# ZeroGecko110BreakoutV1_1.net
KiCad netlist of a schematic drawn in EAGLE
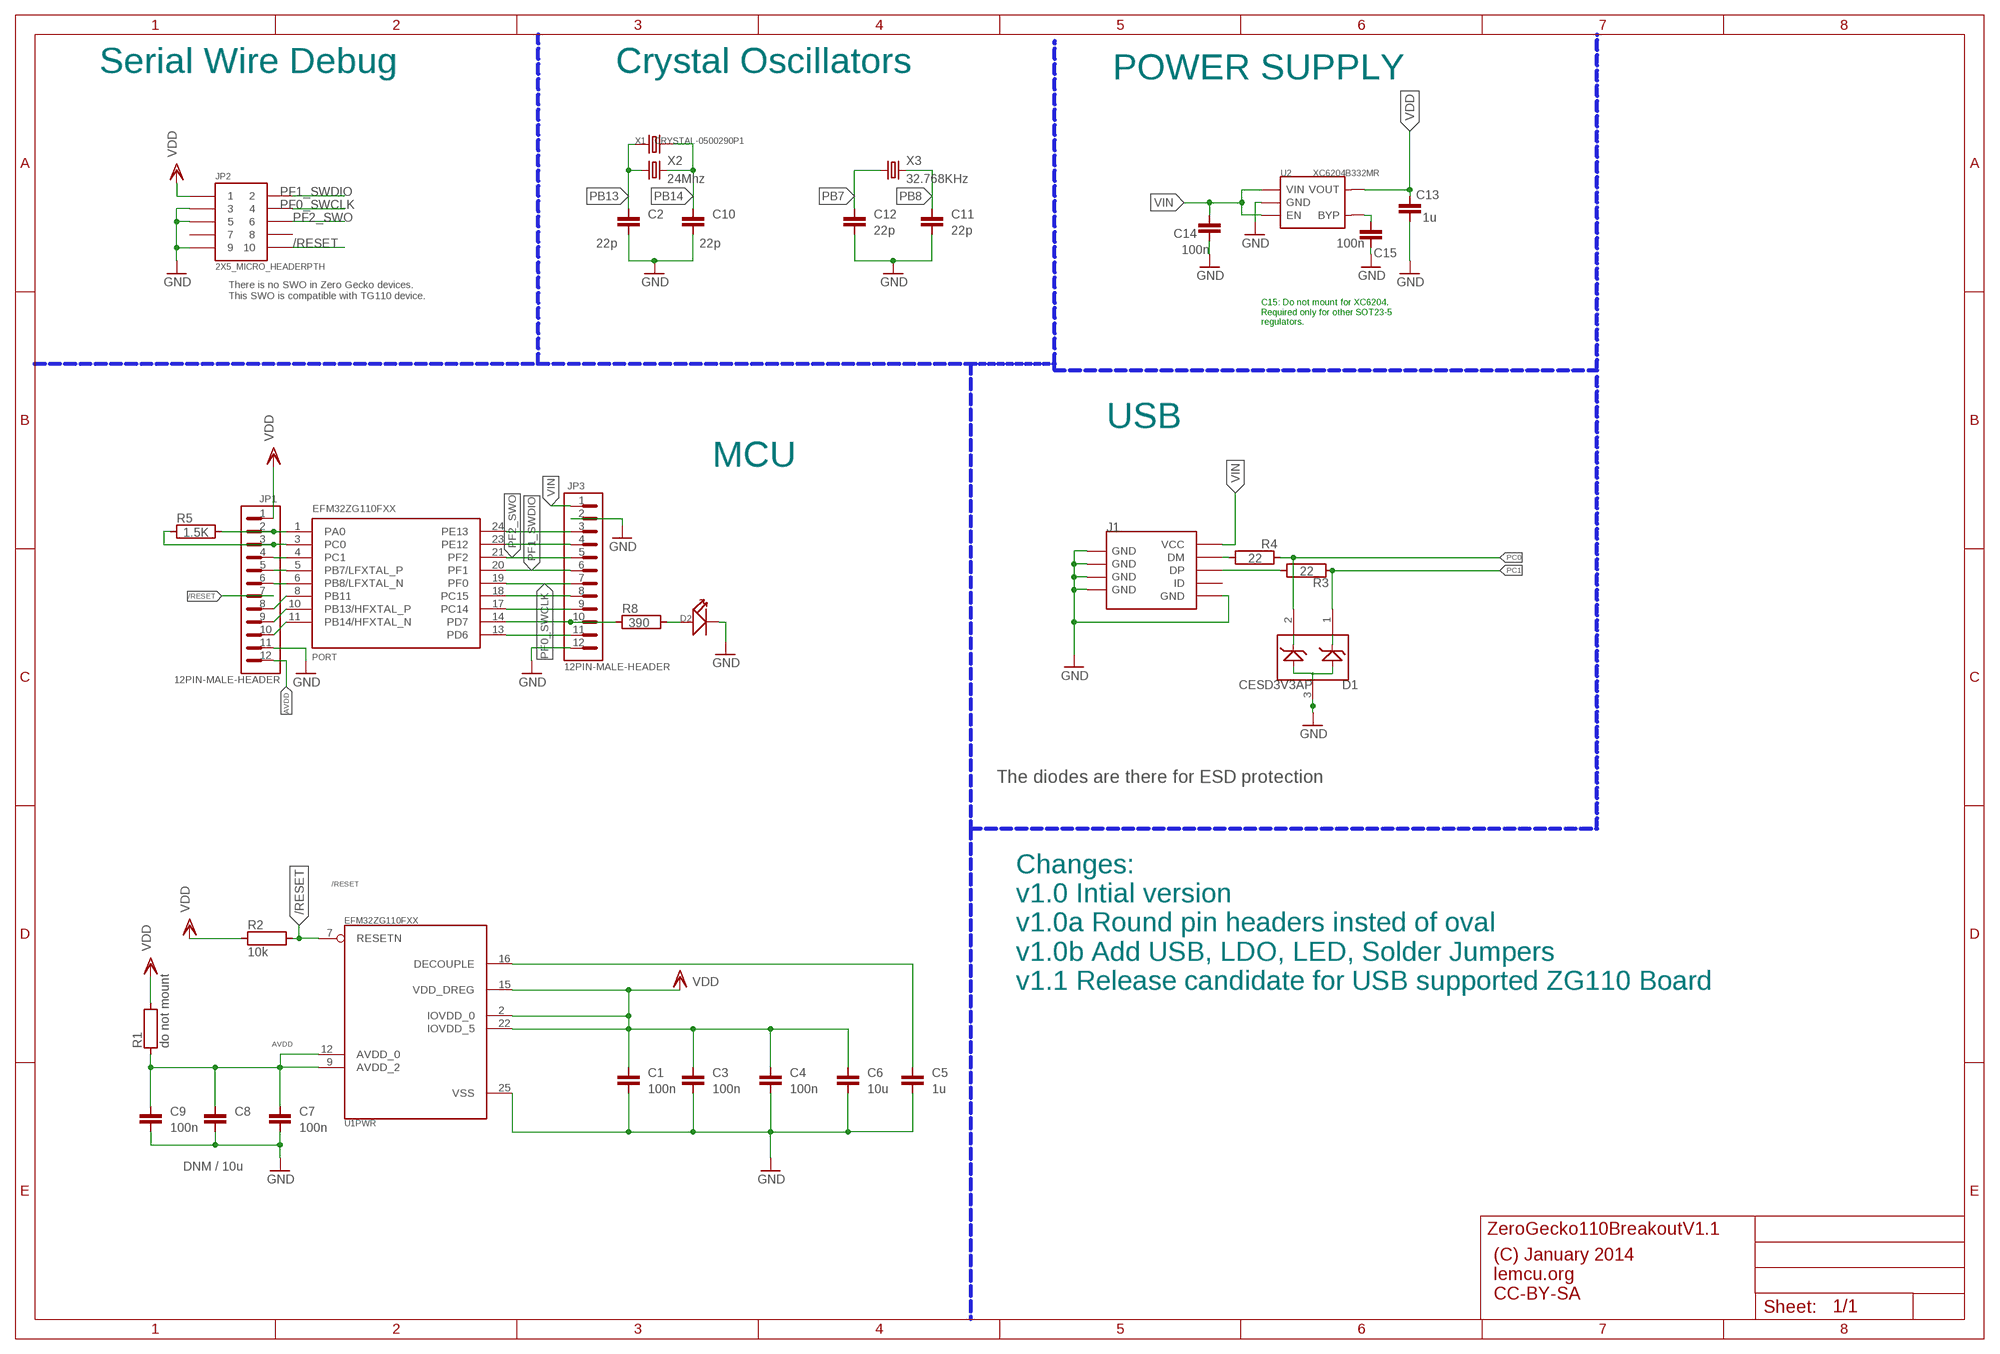
[diagram p0: schematic, sheet 1]

(export (version "E")
  (design (tool "Eeschema 10.0.6"))
  (components
    (comp (ref "C1")
      (value "100n")
      (footprint "eagle-import:C0603")
      (libsource (lib "eagle-import") (part "C0603"))
    )
    (comp (ref "C2")
      (value "22p")
      (footprint "eagle-import:C0603")
      (libsource (lib "eagle-import") (part "C0603"))
    )
    (comp (ref "C3")
      (value "100n")
      (footprint "eagle-import:C0603")
      (libsource (lib "eagle-import") (part "C0603"))
    )
    (comp (ref "C4")
      (value "100n")
      (footprint "eagle-import:C0603")
      (libsource (lib "eagle-import") (part "C0603"))
    )
    (comp (ref "C5")
      (value "1u")
      (footprint "eagle-import:C0805")
      (libsource (lib "eagle-import") (part "C0805"))
    )
    (comp (ref "C6")
      (value "10u")
      (footprint "eagle-import:C0805")
      (libsource (lib "eagle-import") (part "C0805"))
    )
    (comp (ref "C7")
      (value "100n")
      (footprint "eagle-import:C0603")
      (libsource (lib "eagle-import") (part "C0603"))
    )
    (comp (ref "C8")
      (value "DNM / 10u")
      (footprint "eagle-import:C0805")
      (libsource (lib "eagle-import") (part "C0805"))
    )
    (comp (ref "C9")
      (value "100n")
      (footprint "eagle-import:C0603")
      (libsource (lib "eagle-import") (part "C0603"))
    )
    (comp (ref "C10")
      (value "22p")
      (footprint "eagle-import:C0603")
      (libsource (lib "eagle-import") (part "C0603"))
    )
    (comp (ref "C11")
      (value "22p")
      (footprint "eagle-import:C0603")
      (libsource (lib "eagle-import") (part "C0603"))
    )
    (comp (ref "C12")
      (value "22p")
      (footprint "eagle-import:C0603")
      (libsource (lib "eagle-import") (part "C0603"))
    )
    (comp (ref "C13")
      (value "1u")
      (footprint "eagle-import:C0805")
      (libsource (lib "eagle-import") (part "C0805"))
    )
    (comp (ref "C14")
      (value "100n")
      (footprint "eagle-import:C0805")
      (libsource (lib "eagle-import") (part "C0805"))
    )
    (comp (ref "C15")
      (value "100n")
      (footprint "eagle-import:C0805")
      (libsource (lib "eagle-import") (part "C0805"))
    )
    (comp (ref "D1")
      (value "CESD3V3AP")
      (footprint "eagle-import:SOT23")
      (libsource (lib "eagle-import") (part "D-ESD-3P"))
    )
    (comp (ref "D2")
      (value "LED")
      (footprint "eagle-import:LED0603")
      (libsource (lib "eagle-import") (part "LED"))
    )
    (comp (ref "J1")
      (value "USB-MINIUSB-5P-MICRO")
      (footprint "eagle-import:MICRO-USB")
      (libsource (lib "eagle-import") (part "USB-MINIUSB-5P-MICRO"))
    )
    (comp (ref "JP1")
      (value "12PIN-MALE-HEADER")
      (footprint "eagle-import:12P-2.54MM")
      (libsource (lib "eagle-import") (part "12PIN-MALE-HEADER"))
    )
    (comp (ref "JP2")
      (value "2X5_MICRO_HEADERPTH")
      (footprint "eagle-import:2X5_1.27MM_PTH")
      (libsource (lib "eagle-import") (part "2X5_MICRO_HEADERPTH"))
    )
    (comp (ref "JP3")
      (value "12PIN-MALE-HEADER")
      (footprint "eagle-import:12P-2.54MM")
      (libsource (lib "eagle-import") (part "12PIN-MALE-HEADER"))
    )
    (comp (ref "R1")
      (value "do not mount")
      (footprint "eagle-import:R0805")
      (libsource (lib "eagle-import") (part "R0805"))
    )
    (comp (ref "R2")
      (value "10k")
      (footprint "eagle-import:R0603")
      (libsource (lib "eagle-import") (part "R0603"))
    )
    (comp (ref "R3")
      (value "22")
      (footprint "eagle-import:R0603")
      (libsource (lib "eagle-import") (part "R0603"))
    )
    (comp (ref "R4")
      (value "22")
      (footprint "eagle-import:R0603")
      (libsource (lib "eagle-import") (part "R0603"))
    )
    (comp (ref "R5")
      (value "1.5K")
      (footprint "eagle-import:R0603")
      (libsource (lib "eagle-import") (part "R0603"))
    )
    (comp (ref "R8")
      (value "390")
      (footprint "eagle-import:R0603")
      (libsource (lib "eagle-import") (part "R0603"))
    )
    (comp (ref "U1")
      (value "EFM32ZG110FXX")
      (footprint "eagle-import:QFN24")
      (libsource (lib "eagle-import") (part "EFM32ZG110FXX"))
    )
    (comp (ref "U2")
      (value "XC6204B332MR")
      (footprint "eagle-import:SOT23-5")
      (libsource (lib "eagle-import") (part "XC6204B332MR"))
    )
    (comp (ref "X1")
      (value "CRYSTAL-0500290P1")
      (footprint "eagle-import:2P-SMD-5.0X3.2")
      (libsource (lib "eagle-import") (part "CRYSTAL-0500290P1"))
    )
    (comp (ref "X2")
      (value "24Mhz")
      (footprint "eagle-import:HC49U-V")
      (libsource (lib "eagle-import") (part "CRYSTALHC49U-V"))
    )
    (comp (ref "X3")
      (value "32.768KHz")
      (footprint "eagle-import:TC26V")
      (libsource (lib "eagle-import") (part "CRYSTALTC26V"))
    )
  )
  (nets
    (net (code "1") (name "AVDD") (class "Default")
      (node (ref "C7") (pin "2") (pinfunction "2_2") (pintype "passive"))
      (node (ref "C8") (pin "2") (pinfunction "2_2") (pintype "passive"))
      (node (ref "C9") (pin "2") (pinfunction "2_2") (pintype "passive"))
      (node (ref "JP1") (pin "12") (pinfunction "12_12") (pintype "bidirectional"))
      (node (ref "R1") (pin "1") (pinfunction "1_1") (pintype "passive"))
      (node (ref "U1") (pin "12") (pinfunction "AVDD_0_12") (pintype "power_in"))
      (node (ref "U1") (pin "9") (pinfunction "AVDD_2_9") (pintype "power_in"))
    )
    (net (code "2") (name "GND") (class "Default")
      (node (ref "C1") (pin "1") (pinfunction "1_1") (pintype "passive"))
      (node (ref "C10") (pin "1") (pinfunction "1_1") (pintype "passive"))
      (node (ref "C11") (pin "1") (pinfunction "1_1") (pintype "passive"))
      (node (ref "C12") (pin "1") (pinfunction "1_1") (pintype "passive"))
      (node (ref "C13") (pin "1") (pinfunction "1_1") (pintype "passive"))
      (node (ref "C14") (pin "1") (pinfunction "1_1") (pintype "passive"))
      (node (ref "C15") (pin "1") (pinfunction "1_1") (pintype "passive"))
      (node (ref "C2") (pin "1") (pinfunction "1_1") (pintype "passive"))
      (node (ref "C3") (pin "1") (pinfunction "1_1") (pintype "passive"))
      (node (ref "C4") (pin "1") (pinfunction "1_1") (pintype "passive"))
      (node (ref "C5") (pin "1") (pinfunction "1_1") (pintype "passive"))
      (node (ref "C6") (pin "1") (pinfunction "1_1") (pintype "passive"))
      (node (ref "C7") (pin "1") (pinfunction "1_1") (pintype "passive"))
      (node (ref "C8") (pin "1") (pinfunction "1_1") (pintype "passive"))
      (node (ref "C9") (pin "1") (pinfunction "1_1") (pintype "passive"))
      (node (ref "D1") (pin "3") (pinfunction "3_3") (pintype "bidirectional"))
      (node (ref "D2") (pin "-") (pinfunction "-_-") (pintype "passive"))
      (node (ref "J1") (pin "5") (pinfunction "GND_5") (pintype "bidirectional"))
      (node (ref "J1") (pin "S1") (pinfunction "GND_S1") (pintype "bidirectional"))
      (node (ref "J1") (pin "S2") (pinfunction "GND_S2") (pintype "bidirectional"))
      (node (ref "J1") (pin "S3") (pinfunction "GND_S3") (pintype "bidirectional"))
      (node (ref "J1") (pin "S4") (pinfunction "GND_S4") (pintype "bidirectional"))
      (node (ref "J1") (pin "S5") (pinfunction "GND_S5") (pintype "bidirectional"))
      (node (ref "J1") (pin "S6") (pinfunction "GND_S6") (pintype "bidirectional"))
      (node (ref "JP1") (pin "11") (pinfunction "11_11") (pintype "bidirectional"))
      (node (ref "JP2") (pin "3") (pinfunction "3_3") (pintype "bidirectional"))
      (node (ref "JP2") (pin "5") (pinfunction "5_5") (pintype "bidirectional"))
      (node (ref "JP2") (pin "9") (pinfunction "9_9") (pintype "bidirectional"))
      (node (ref "JP3") (pin "12") (pinfunction "12_12") (pintype "bidirectional"))
      (node (ref "JP3") (pin "2") (pinfunction "2_2") (pintype "bidirectional"))
      (node (ref "U1") (pin "25") (pinfunction "VSS_25") (pintype "power_in"))
      (node (ref "U2") (pin "2") (pinfunction "GND_2") (pintype "bidirectional"))
    )
    (net (code "3") (name "Net-(D2-Pad+)") (class "Default")
      (node (ref "D2") (pin "+") (pinfunction "+_+") (pintype "passive"))
      (node (ref "R8") (pin "2") (pinfunction "2_2") (pintype "passive"))
    )
    (net (code "4") (name "Net-(J1-DM)") (class "Default")
      (node (ref "J1") (pin "2") (pinfunction "DM_2") (pintype "bidirectional"))
      (node (ref "R4") (pin "1") (pinfunction "1_1") (pintype "passive"))
    )
    (net (code "5") (name "Net-(J1-DP)") (class "Default")
      (node (ref "J1") (pin "3") (pinfunction "DP_3") (pintype "bidirectional"))
      (node (ref "R3") (pin "1") (pinfunction "1_1") (pintype "passive"))
    )
    (net (code "6") (name "Net-(U1A-PA0)") (class "Default")
      (node (ref "JP1") (pin "2") (pinfunction "2_2") (pintype "bidirectional"))
      (node (ref "R5") (pin "2") (pinfunction "2_2") (pintype "passive"))
      (node (ref "U1") (pin "1") (pinfunction "PA0_1") (pintype "bidirectional"))
    )
    (net (code "7") (name "Net-(U1A-PB11)") (class "Default")
      (node (ref "JP1") (pin "8") (pinfunction "8_8") (pintype "bidirectional"))
      (node (ref "U1") (pin "8") (pinfunction "PB11_8") (pintype "bidirectional"))
    )
    (net (code "8") (name "Net-(U1A-PC14)") (class "Default")
      (node (ref "JP3") (pin "9") (pinfunction "9_9") (pintype "bidirectional"))
      (node (ref "U1") (pin "17") (pinfunction "PC14_17") (pintype "bidirectional"))
    )
    (net (code "9") (name "Net-(U1A-PC15)") (class "Default")
      (node (ref "JP3") (pin "8") (pinfunction "8_8") (pintype "bidirectional"))
      (node (ref "U1") (pin "18") (pinfunction "PC15_18") (pintype "bidirectional"))
    )
    (net (code "10") (name "Net-(U1A-PD6)") (class "Default")
      (node (ref "JP3") (pin "11") (pinfunction "11_11") (pintype "bidirectional"))
      (node (ref "U1") (pin "13") (pinfunction "PD6_13") (pintype "bidirectional"))
    )
    (net (code "11") (name "Net-(U1A-PD7)") (class "Default")
      (node (ref "JP3") (pin "10") (pinfunction "10_10") (pintype "bidirectional"))
      (node (ref "R8") (pin "1") (pinfunction "1_1") (pintype "passive"))
      (node (ref "U1") (pin "14") (pinfunction "PD7_14") (pintype "bidirectional"))
    )
    (net (code "12") (name "Net-(U1A-PE12)") (class "Default")
      (node (ref "JP3") (pin "4") (pinfunction "4_4") (pintype "bidirectional"))
      (node (ref "U1") (pin "23") (pinfunction "PE12_23") (pintype "bidirectional"))
    )
    (net (code "13") (name "Net-(U1A-PE13)") (class "Default")
      (node (ref "JP3") (pin "3") (pinfunction "3_3") (pintype "bidirectional"))
      (node (ref "U1") (pin "24") (pinfunction "PE13_24") (pintype "bidirectional"))
    )
    (net (code "14") (name "Net-(U1B-DECOUPLE)") (class "Default")
      (node (ref "C5") (pin "2") (pinfunction "2_2") (pintype "passive"))
      (node (ref "U1") (pin "16") (pinfunction "DECOUPLE_16") (pintype "power_in"))
    )
    (net (code "15") (name "Net-(U2-BYP)") (class "Default")
      (node (ref "C15") (pin "2") (pinfunction "2_2") (pintype "passive"))
      (node (ref "U2") (pin "4") (pinfunction "BYP_4") (pintype "bidirectional"))
    )
    (net (code "16") (name "PB7") (class "Default")
      (node (ref "C12") (pin "2") (pinfunction "2_2") (pintype "passive"))
      (node (ref "JP1") (pin "5") (pinfunction "5_5") (pintype "bidirectional"))
      (node (ref "U1") (pin "5") (pinfunction "PB7/LFXTAL_P_5") (pintype "bidirectional"))
      (node (ref "X3") (pin "1") (pinfunction "1_1") (pintype "passive"))
    )
    (net (code "17") (name "PB8") (class "Default")
      (node (ref "C11") (pin "2") (pinfunction "2_2") (pintype "passive"))
      (node (ref "JP1") (pin "6") (pinfunction "6_6") (pintype "bidirectional"))
      (node (ref "U1") (pin "6") (pinfunction "PB8/LFXTAL_N_6") (pintype "bidirectional"))
      (node (ref "X3") (pin "2") (pinfunction "2_2") (pintype "passive"))
    )
    (net (code "18") (name "PB13") (class "Default")
      (node (ref "C2") (pin "2") (pinfunction "2_2") (pintype "passive"))
      (node (ref "JP1") (pin "9") (pinfunction "9_9") (pintype "bidirectional"))
      (node (ref "U1") (pin "10") (pinfunction "PB13/HFXTAL_P_10") (pintype "bidirectional"))
      (node (ref "X1") (pin "1") (pinfunction "1_1") (pintype "passive"))
      (node (ref "X2") (pin "1") (pinfunction "1_1") (pintype "passive"))
    )
    (net (code "19") (name "PB14") (class "Default")
      (node (ref "C10") (pin "2") (pinfunction "2_2") (pintype "passive"))
      (node (ref "JP1") (pin "10") (pinfunction "10_10") (pintype "bidirectional"))
      (node (ref "U1") (pin "11") (pinfunction "PB14/HFXTAL_N_11") (pintype "bidirectional"))
      (node (ref "X1") (pin "2") (pinfunction "2_2") (pintype "passive"))
      (node (ref "X2") (pin "2") (pinfunction "2_2") (pintype "passive"))
    )
    (net (code "20") (name "PC0") (class "Default")
      (node (ref "D1") (pin "2") (pinfunction "2_2") (pintype "bidirectional"))
      (node (ref "JP1") (pin "3") (pinfunction "3_3") (pintype "bidirectional"))
      (node (ref "R4") (pin "2") (pinfunction "2_2") (pintype "passive"))
      (node (ref "R5") (pin "1") (pinfunction "1_1") (pintype "passive"))
      (node (ref "U1") (pin "3") (pinfunction "PC0_3") (pintype "bidirectional"))
    )
    (net (code "21") (name "PC1") (class "Default")
      (node (ref "D1") (pin "1") (pinfunction "1_1") (pintype "bidirectional"))
      (node (ref "JP1") (pin "4") (pinfunction "4_4") (pintype "bidirectional"))
      (node (ref "R3") (pin "2") (pinfunction "2_2") (pintype "passive"))
      (node (ref "U1") (pin "4") (pinfunction "PC1_4") (pintype "bidirectional"))
    )
    (net (code "22") (name "PF0_SWCLK") (class "Default")
      (node (ref "JP2") (pin "4") (pinfunction "4_4") (pintype "bidirectional"))
      (node (ref "JP3") (pin "7") (pinfunction "7_7") (pintype "bidirectional"))
      (node (ref "U1") (pin "19") (pinfunction "PF0_19") (pintype "bidirectional"))
    )
    (net (code "23") (name "PF1_SWDIO") (class "Default")
      (node (ref "JP2") (pin "2") (pinfunction "2_2") (pintype "bidirectional"))
      (node (ref "JP3") (pin "6") (pinfunction "6_6") (pintype "bidirectional"))
      (node (ref "U1") (pin "20") (pinfunction "PF1_20") (pintype "bidirectional"))
    )
    (net (code "24") (name "PF2_SWO") (class "Default")
      (node (ref "JP2") (pin "6") (pinfunction "6_6") (pintype "bidirectional"))
      (node (ref "JP3") (pin "5") (pinfunction "5_5") (pintype "bidirectional"))
      (node (ref "U1") (pin "21") (pinfunction "PF2_21") (pintype "bidirectional"))
    )
    (net (code "25") (name "VDD") (class "Default")
      (node (ref "C1") (pin "2") (pinfunction "2_2") (pintype "passive"))
      (node (ref "C13") (pin "2") (pinfunction "2_2") (pintype "passive"))
      (node (ref "C3") (pin "2") (pinfunction "2_2") (pintype "passive"))
      (node (ref "C4") (pin "2") (pinfunction "2_2") (pintype "passive"))
      (node (ref "C6") (pin "2") (pinfunction "2_2") (pintype "passive"))
      (node (ref "JP1") (pin "1") (pinfunction "1_1") (pintype "bidirectional"))
      (node (ref "JP2") (pin "1") (pinfunction "1_1") (pintype "bidirectional"))
      (node (ref "R1") (pin "2") (pinfunction "2_2") (pintype "passive"))
      (node (ref "R2") (pin "1") (pinfunction "1_1") (pintype "passive"))
      (node (ref "U1") (pin "15") (pinfunction "VDD_DREG_15") (pintype "power_in"))
      (node (ref "U1") (pin "2") (pinfunction "IOVDD_0_2") (pintype "power_in"))
      (node (ref "U1") (pin "22") (pinfunction "IOVDD_5_22") (pintype "power_in"))
      (node (ref "U2") (pin "5") (pinfunction "VOUT_5") (pintype "bidirectional"))
    )
    (net (code "26") (name "VIN") (class "Default")
      (node (ref "C14") (pin "2") (pinfunction "2_2") (pintype "passive"))
      (node (ref "J1") (pin "1") (pinfunction "VCC_1") (pintype "bidirectional"))
      (node (ref "JP3") (pin "1") (pinfunction "1_1") (pintype "bidirectional"))
      (node (ref "U2") (pin "1") (pinfunction "VIN_1") (pintype "bidirectional"))
      (node (ref "U2") (pin "3") (pinfunction "EN_3") (pintype "bidirectional"))
    )
    (net (code "27") (name "unconnected-(J1-ID-Pad4)") (class "Default")
      (node (ref "J1") (pin "4") (pinfunction "ID_4") (pintype "bidirectional"))
    )
    (net (code "28") (name "unconnected-(JP2-Pad7)") (class "Default")
      (node (ref "JP2") (pin "7") (pinfunction "7_7") (pintype "bidirectional"))
    )
    (net (code "29") (name "unconnected-(JP2-Pad8)") (class "Default")
      (node (ref "JP2") (pin "8") (pinfunction "8_8") (pintype "bidirectional"))
    )
    (net (code "30") (name "{slash}RESET") (class "Default")
      (node (ref "JP1") (pin "7") (pinfunction "7_7") (pintype "bidirectional"))
      (node (ref "JP2") (pin "10") (pinfunction "10_10") (pintype "bidirectional"))
      (node (ref "R2") (pin "2") (pinfunction "2_2") (pintype "passive"))
      (node (ref "U1") (pin "7") (pinfunction "RESETN_7") (pintype "passive"))
    )
  )
)
